# Quick_Dev_board_2021-04-23.net
KiCad netlist of a schematic drawn in EasyEDA
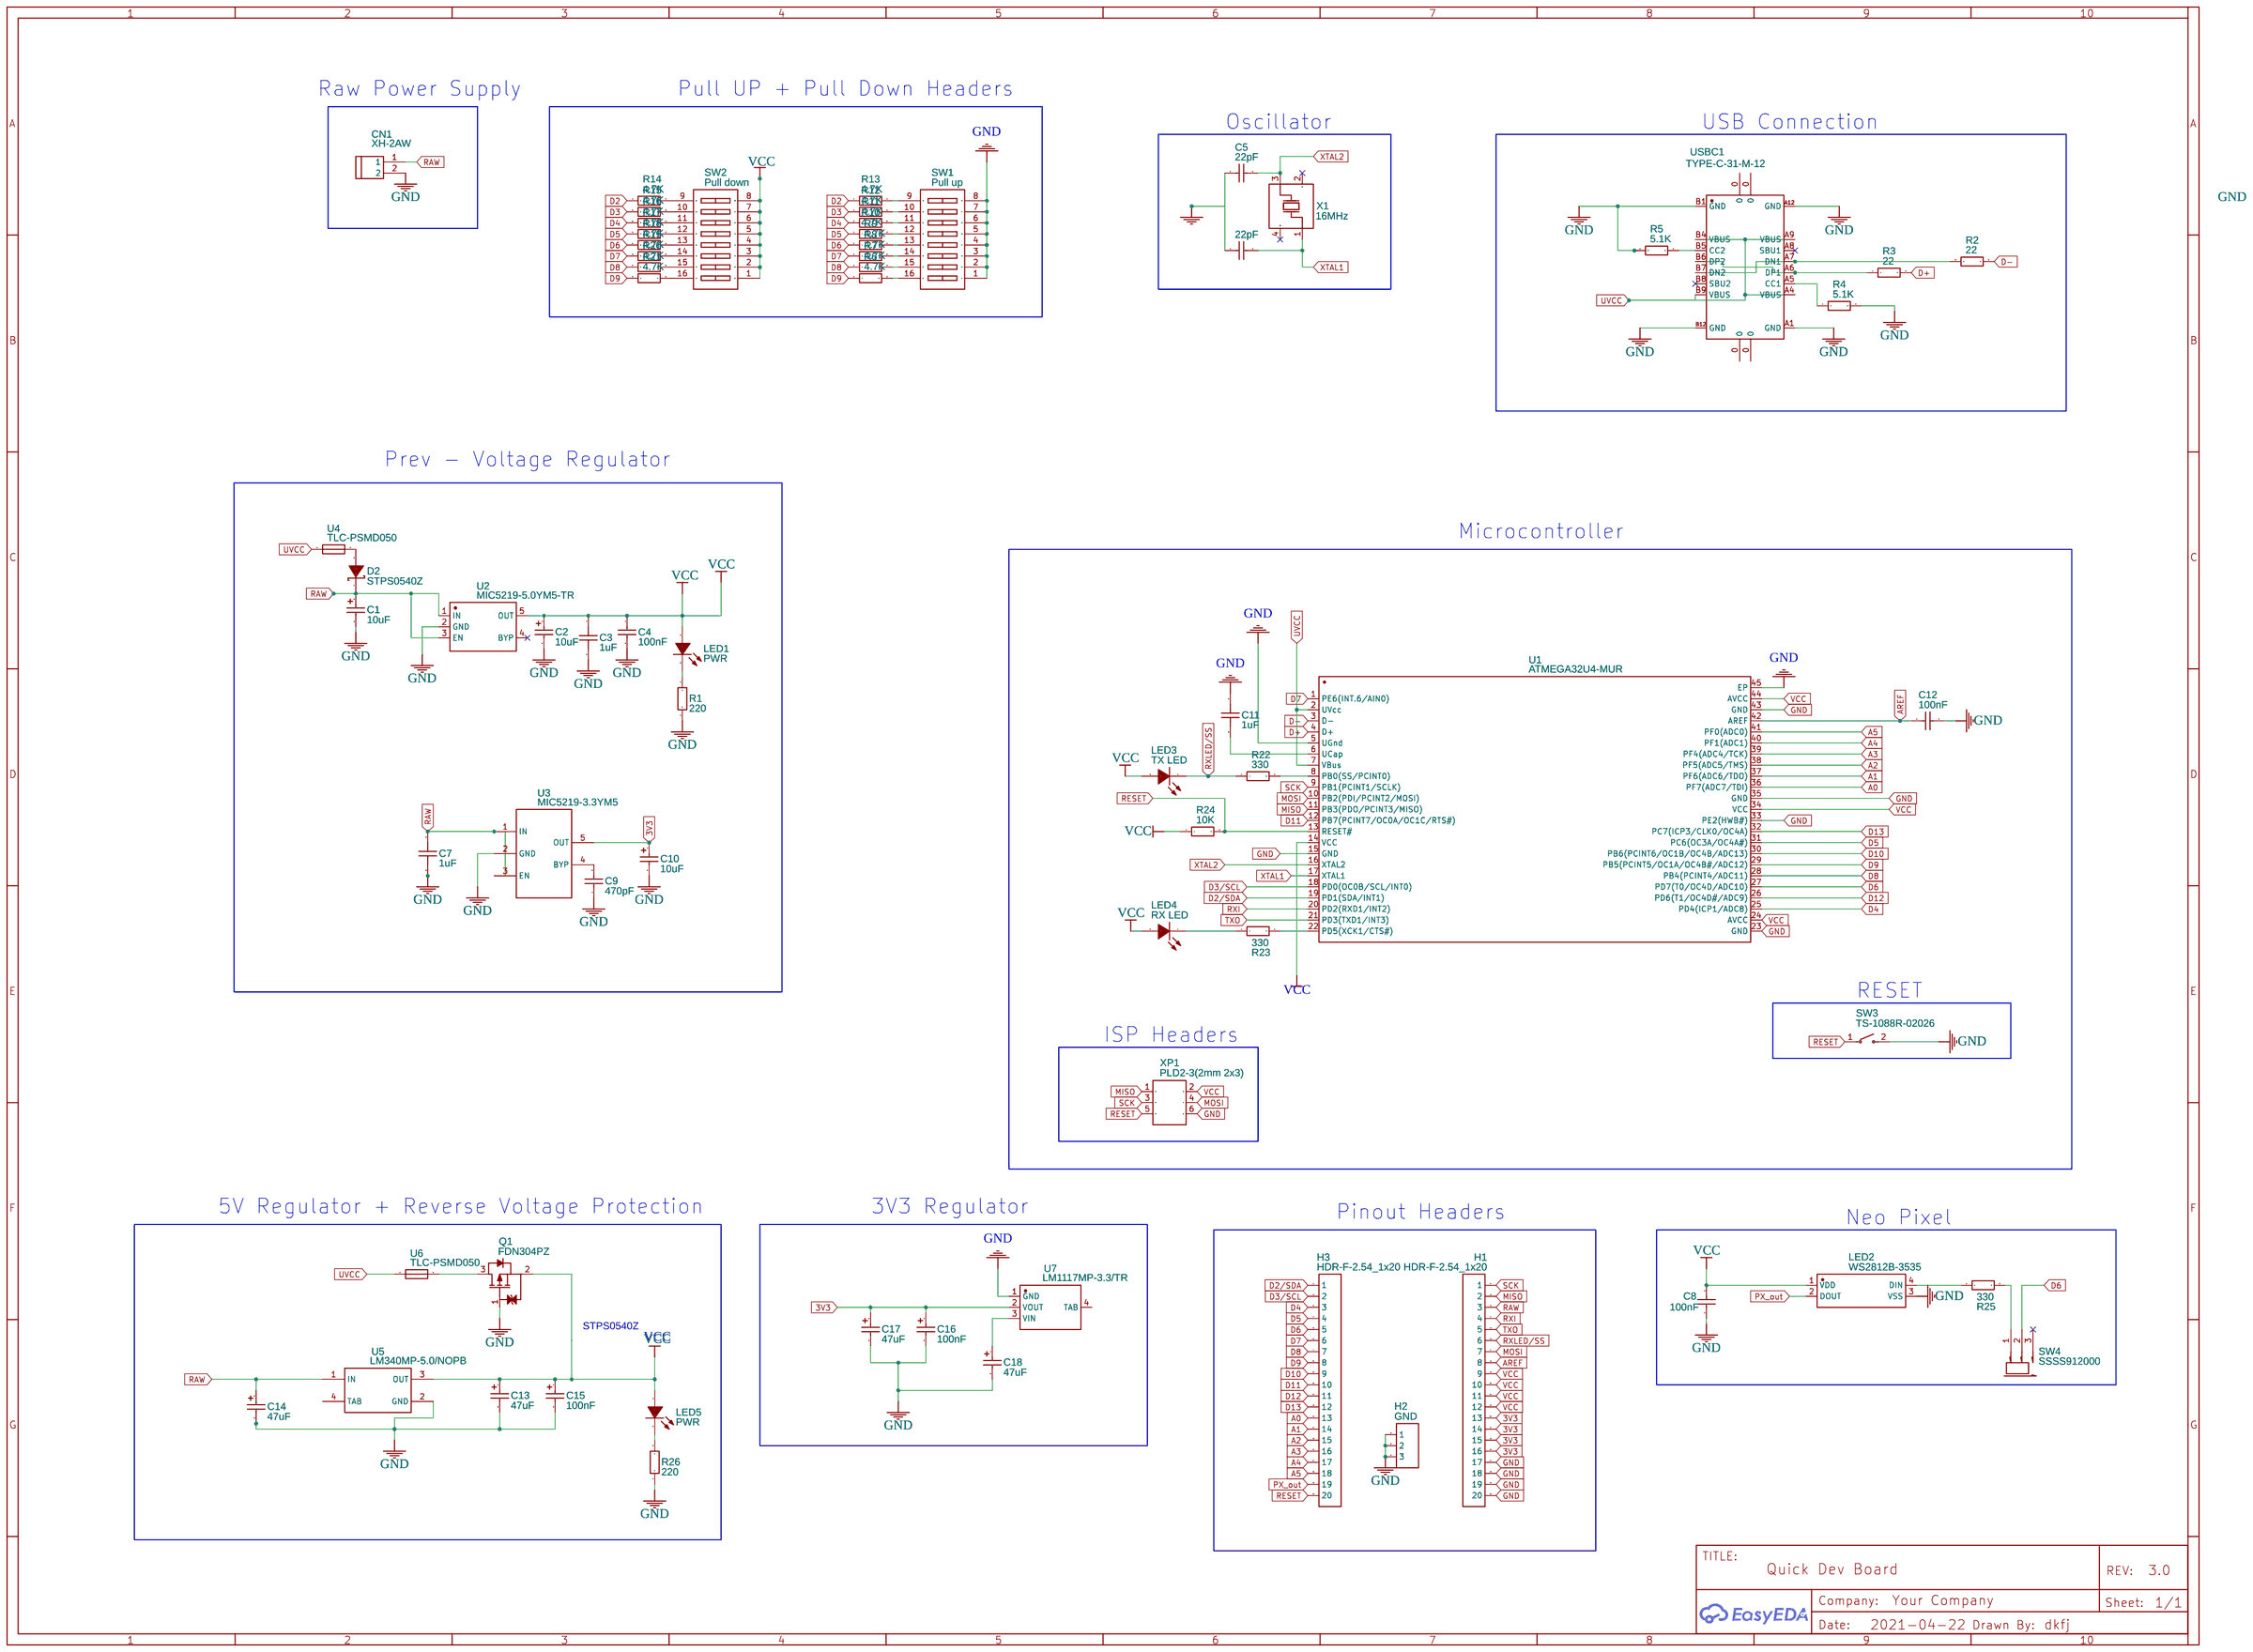
[diagram p0: schematic sheet]

(export (version "E")
  (design (tool "Eeschema 10.0.6"))
  (components
    (comp (ref "C1")
      (value "10uF")
      (fields
        (field (name "BOM_Manufacturer Part") "TAJA106K016RNJ")
        (field (name "BOM_Supplier Part") "C7171")
      )
      (libsource (lib "") (part "TAJA106K016RNJ"))
    )
    (comp (ref "C2")
      (value "10uF")
      (fields
        (field (name "BOM_Manufacturer Part") "TAJA106K016RNJ")
        (field (name "BOM_Supplier Part") "C7171")
      )
      (libsource (lib "") (part "TAJA106K016RNJ"))
    )
    (comp (ref "C3")
      (value "1uF")
      (fields
        (field (name "BOM_Manufacturer Part") "CL05A105KA5NQNC")
        (field (name "BOM_Supplier Part") "C52923")
      )
      (libsource (lib "") (part "CL05A105KA5NQNC"))
    )
    (comp (ref "C4")
      (value "100nF")
      (fields
        (field (name "BOM_Manufacturer Part") "CL05B104KO5NNNC")
        (field (name "BOM_Supplier Part") "C1525")
      )
      (libsource (lib "") (part "CL05B104KO5NNNC_1"))
    )
    (comp (ref "C5")
      (value "22pF")
      (fields
        (field (name "BOM_Manufacturer Part") "0402CG220J500NT")
        (field (name "BOM_Supplier Part") "C1555")
      )
      (libsource (lib "") (part "0402CG220J500NT"))
    )
    (comp (ref "C6")
      (value "22pF")
      (fields
        (field (name "BOM_Manufacturer Part") "0402CG220J500NT")
        (field (name "BOM_Supplier Part") "C1555")
      )
      (libsource (lib "") (part "0402CG220J500NT"))
    )
    (comp (ref "C7")
      (value "1uF")
      (fields
        (field (name "BOM_Manufacturer Part") "CL05A105KA5NQNC")
        (field (name "BOM_Supplier Part") "C52923")
      )
      (libsource (lib "") (part "CL05A105KA5NQNC"))
    )
    (comp (ref "C8")
      (value "100nF")
      (fields
        (field (name "BOM_Manufacturer Part") "CL05B104KO5NNNC")
        (field (name "BOM_Supplier Part") "C1525")
      )
      (libsource (lib "") (part "CL05B104KO5NNNC_1"))
    )
    (comp (ref "C9")
      (value "470pF")
      (fields
        (field (name "BOM_Manufacturer Part") "0402B471K500NT")
        (field (name "BOM_Supplier Part") "C1537")
      )
      (libsource (lib "") (part "0402B471K500NT"))
    )
    (comp (ref "C10")
      (value "10uF")
      (fields
        (field (name "BOM_Manufacturer Part") "TAJA106K016RNJ")
        (field (name "BOM_Supplier Part") "C7171")
      )
      (libsource (lib "") (part "TAJA106K016RNJ"))
    )
    (comp (ref "C11")
      (value "1uF")
      (fields
        (field (name "BOM_Manufacturer Part") "CL05A105KA5NQNC")
        (field (name "BOM_Supplier Part") "C52923")
      )
      (libsource (lib "") (part "CL05A105KA5NQNC"))
    )
    (comp (ref "C12")
      (value "100nF")
      (fields
        (field (name "BOM_Manufacturer Part") "CL05B104KO5NNNC")
        (field (name "BOM_Supplier Part") "C1525")
      )
      (libsource (lib "") (part "CL05B104KO5NNNC"))
    )
    (comp (ref "C13")
      (value "47uF")
      (fields
        (field (name "BOM_Manufacturer Part") "TAJA106K016RNJ")
        (field (name "BOM_Supplier Part") "C7171")
      )
      (libsource (lib "") (part "TAJA106K016RNJ"))
    )
    (comp (ref "C14")
      (value "47uF")
      (fields
        (field (name "BOM_Manufacturer Part") "TAJA106K016RNJ")
        (field (name "BOM_Supplier Part") "C7171")
      )
      (libsource (lib "") (part "TAJA106K016RNJ"))
    )
    (comp (ref "C15")
      (value "100nF")
      (fields
        (field (name "BOM_Manufacturer Part") "TAJA106K016RNJ")
        (field (name "BOM_Supplier Part") "C7171")
      )
      (libsource (lib "") (part "TAJA106K016RNJ"))
    )
    (comp (ref "C16")
      (value "100nF")
      (fields
        (field (name "BOM_Manufacturer Part") "TAJA106K016RNJ")
        (field (name "BOM_Supplier Part") "C7171")
      )
      (libsource (lib "") (part "TAJA106K016RNJ"))
    )
    (comp (ref "C17")
      (value "47uF")
      (fields
        (field (name "BOM_Manufacturer Part") "TAJA106K016RNJ")
        (field (name "BOM_Supplier Part") "C7171")
      )
      (libsource (lib "") (part "TAJA106K016RNJ"))
    )
    (comp (ref "C18")
      (value "47uF")
      (fields
        (field (name "BOM_Manufacturer Part") "TAJA106K016RNJ")
        (field (name "BOM_Supplier Part") "C7171")
      )
      (libsource (lib "") (part "TAJA106K016RNJ"))
    )
    (comp (ref "CN1")
      (value "XH-2AW")
      (fields (field (name "BOM_Supplier Part") "C33132"))
      (libsource (lib "") (part "XH-2AW"))
    )
    (comp (ref "D2")
      (value "STPS0540Z")
      (fields (field (name "BOM_Supplier Part") "C181835"))
      (libsource (lib "") (part "STPS0540Z"))
    )
    (comp (ref "H1")
      (value "HDR-F-2.54_1x20")
      (fields (field (name "BOM_Supplier Part") "C50984"))
      (libsource (lib "") (part "HDR-F-2.54_1x20"))
    )
    (comp (ref "H2")
      (value "GND")
      (fields (field (name "BOM_Supplier Part") "C146690"))
      (libsource (lib "") (part "HDR-F-2.54_1x3"))
    )
    (comp (ref "H3")
      (value "HDR-F-2.54_1x20")
      (fields (field (name "BOM_Supplier Part") "C50984"))
      (libsource (lib "") (part "HDR-F-2.54_1x20_1"))
    )
    (comp (ref "LED1")
      (value "PWR")
      (fields (field (name "BOM_Manufacturer Part") "KT-0603R") (field (name "BOM_Supplier Part") "C2286"))
      (libsource (lib "") (part "KT-0603R"))
    )
    (comp (ref "LED2")
      (value "WS2812B-3535")
      (fields (field (name "BOM_Supplier Part") "C114583"))
      (libsource (lib "") (part "WS2812B-3535"))
    )
    (comp (ref "LED3")
      (value "TX LED")
      (fields
        (field (name "BOM_Manufacturer Part") "17-21SUYC/TR8")
        (field (name "BOM_Supplier Part") "C2296")
      )
      (libsource (lib "") (part "17-21SUYC/TR8"))
    )
    (comp (ref "LED4")
      (value "RX LED")
      (fields
        (field (name "BOM_Manufacturer Part") "17-21SUYC/TR8")
        (field (name "BOM_Supplier Part") "C2296")
      )
      (libsource (lib "") (part "17-21SUYC/TR8"))
    )
    (comp (ref "LED5")
      (value "PWR")
      (fields (field (name "BOM_Manufacturer Part") "KT-0603R") (field (name "BOM_Supplier Part") "C2286"))
      (libsource (lib "") (part "KT-0603R"))
    )
    (comp (ref "Q1")
      (value "FDN304PZ")
      (fields (field (name "BOM_Supplier Part") "C73273"))
      (libsource (lib "") (part "FDN304PZ"))
    )
    (comp (ref "R1")
      (value "220")
      (fields
        (field (name "BOM_Manufacturer Part") "0603WAF2200T5E")
        (field (name "BOM_Supplier Part") "C22962")
      )
      (libsource (lib "") (part "0603WAF2200T5E"))
    )
    (comp (ref "R2")
      (value "22")
      (fields
        (field (name "BOM_Manufacturer Part") "0402WGF220JTCE")
        (field (name "BOM_Supplier Part") "C25092")
      )
      (libsource (lib "") (part "0402WGF220JTCE"))
    )
    (comp (ref "R3")
      (value "22")
      (fields
        (field (name "BOM_Manufacturer Part") "0402WGF220JTCE")
        (field (name "BOM_Supplier Part") "C25092")
      )
      (libsource (lib "") (part "0402WGF220JTCE"))
    )
    (comp (ref "R4")
      (value "5.1K")
      (fields
        (field (name "BOM_Manufacturer Part") "0402WGF5101TCE")
        (field (name "BOM_Supplier Part") "C25905")
      )
      (libsource (lib "") (part "0402WGF5101TCE"))
    )
    (comp (ref "R5")
      (value "5.1K")
      (fields
        (field (name "BOM_Manufacturer Part") "0402WGF5101TCE")
        (field (name "BOM_Supplier Part") "C25905")
      )
      (libsource (lib "") (part "0402WGF5101TCE"))
    )
    (comp (ref "R6")
      (value "4.7K")
      (fields
        (field (name "BOM_Manufacturer Part") "0402WGF4701TCE")
        (field (name "BOM_Supplier Part") "C25900")
      )
      (libsource (lib "") (part "0402WGF4701TCE"))
    )
    (comp (ref "R7")
      (value "4.7K")
      (fields
        (field (name "BOM_Manufacturer Part") "0402WGF4701TCE")
        (field (name "BOM_Supplier Part") "C25900")
      )
      (libsource (lib "") (part "0402WGF4701TCE"))
    )
    (comp (ref "R8")
      (value "4.7K")
      (fields
        (field (name "BOM_Manufacturer Part") "0402WGF4701TCE")
        (field (name "BOM_Supplier Part") "C25900")
      )
      (libsource (lib "") (part "0402WGF4701TCE"))
    )
    (comp (ref "R9")
      (value "4.7K")
      (fields
        (field (name "BOM_Manufacturer Part") "0402WGF4701TCE")
        (field (name "BOM_Supplier Part") "C25900")
      )
      (libsource (lib "") (part "0402WGF4701TCE"))
    )
    (comp (ref "R10")
      (value "4.7K")
      (fields
        (field (name "BOM_Manufacturer Part") "0402WGF4701TCE")
        (field (name "BOM_Supplier Part") "C25900")
      )
      (libsource (lib "") (part "0402WGF4701TCE"))
    )
    (comp (ref "R11")
      (value "4.7K")
      (fields
        (field (name "BOM_Manufacturer Part") "0402WGF4701TCE")
        (field (name "BOM_Supplier Part") "C25900")
      )
      (libsource (lib "") (part "0402WGF4701TCE"))
    )
    (comp (ref "R12")
      (value "4.7K")
      (fields
        (field (name "BOM_Manufacturer Part") "0402WGF4701TCE")
        (field (name "BOM_Supplier Part") "C25900")
      )
      (libsource (lib "") (part "0402WGF4701TCE"))
    )
    (comp (ref "R13")
      (value "4.7K")
      (fields
        (field (name "BOM_Manufacturer Part") "0402WGF4701TCE")
        (field (name "BOM_Supplier Part") "C25900")
      )
      (libsource (lib "") (part "0402WGF4701TCE"))
    )
    (comp (ref "R14")
      (value "4.7K")
      (fields
        (field (name "BOM_Manufacturer Part") "0402WGF4701TCE")
        (field (name "BOM_Supplier Part") "C25900")
      )
      (libsource (lib "") (part "0402WGF4701TCE"))
    )
    (comp (ref "R15")
      (value "4.7K")
      (fields
        (field (name "BOM_Manufacturer Part") "0402WGF4701TCE")
        (field (name "BOM_Supplier Part") "C25900")
      )
      (libsource (lib "") (part "0402WGF4701TCE"))
    )
    (comp (ref "R16")
      (value "4.7K")
      (fields
        (field (name "BOM_Manufacturer Part") "0402WGF4701TCE")
        (field (name "BOM_Supplier Part") "C25900")
      )
      (libsource (lib "") (part "0402WGF4701TCE"))
    )
    (comp (ref "R17")
      (value "4.7K")
      (fields
        (field (name "BOM_Manufacturer Part") "0402WGF4701TCE")
        (field (name "BOM_Supplier Part") "C25900")
      )
      (libsource (lib "") (part "0402WGF4701TCE"))
    )
    (comp (ref "R18")
      (value "4.7K")
      (fields
        (field (name "BOM_Manufacturer Part") "0402WGF4701TCE")
        (field (name "BOM_Supplier Part") "C25900")
      )
      (libsource (lib "") (part "0402WGF4701TCE"))
    )
    (comp (ref "R19")
      (value "4.7K")
      (fields
        (field (name "BOM_Manufacturer Part") "0402WGF4701TCE")
        (field (name "BOM_Supplier Part") "C25900")
      )
      (libsource (lib "") (part "0402WGF4701TCE"))
    )
    (comp (ref "R20")
      (value "4.7K")
      (fields
        (field (name "BOM_Manufacturer Part") "0402WGF4701TCE")
        (field (name "BOM_Supplier Part") "C25900")
      )
      (libsource (lib "") (part "0402WGF4701TCE"))
    )
    (comp (ref "R21")
      (value "4.7K")
      (fields
        (field (name "BOM_Manufacturer Part") "0402WGF4701TCE")
        (field (name "BOM_Supplier Part") "C25900")
      )
      (libsource (lib "") (part "0402WGF4701TCE"))
    )
    (comp (ref "R22")
      (value "330")
      (fields
        (field (name "BOM_Manufacturer Part") "0402WGF3300TCE")
        (field (name "BOM_Supplier Part") "C25104")
      )
      (libsource (lib "") (part "0402WGF3300TCE"))
    )
    (comp (ref "R23")
      (value "330")
      (fields
        (field (name "BOM_Manufacturer Part") "0402WGF3300TCE")
        (field (name "BOM_Supplier Part") "C25104")
      )
      (libsource (lib "") (part "0402WGF3300TCE"))
    )
    (comp (ref "R24")
      (value "10K")
      (fields
        (field (name "BOM_Manufacturer Part") "0402WGF1002TCE")
        (field (name "BOM_Supplier Part") "C25744")
      )
      (libsource (lib "") (part "0402WGF1002TCE"))
    )
    (comp (ref "R25")
      (value "330")
      (fields
        (field (name "BOM_Manufacturer Part") "0402WGF3300TCE")
        (field (name "BOM_Supplier Part") "C25104")
      )
      (libsource (lib "") (part "0402WGF3300TCE"))
    )
    (comp (ref "R26")
      (value "220")
      (fields
        (field (name "BOM_Manufacturer Part") "0603WAF2200T5E")
        (field (name "BOM_Supplier Part") "C22962")
      )
      (libsource (lib "") (part "0603WAF2200T5E"))
    )
    (comp (ref "SW1")
      (value "Pull up")
      (fields
        (field (name "BOM_Manufacturer Part") "DSHP08TS-S")
        (field (name "BOM_Supplier Part") "C319047")
      )
      (libsource (lib "") (part "DSHP08TS-S"))
    )
    (comp (ref "SW2")
      (value "Pull down")
      (fields
        (field (name "BOM_Manufacturer Part") "DSHP08TS-S")
        (field (name "BOM_Supplier Part") "C319047")
      )
      (libsource (lib "") (part "DSHP08TS-S"))
    )
    (comp (ref "SW3")
      (value "TS-1088R-02026")
      (fields (field (name "BOM_Supplier Part") "C455280"))
      (libsource (lib "") (part "TS-1088R-02026"))
    )
    (comp (ref "SW4")
      (value "SSSS912000")
      (fields (field (name "BOM_Supplier Part") "C125042"))
      (libsource (lib "") (part "SSSS912000"))
    )
    (comp (ref "U1")
      (value "ATMEGA32U4-MUR")
      (fields (field (name "BOM_Supplier Part") "C45874"))
      (libsource (lib "") (part "ATMEGA32U4-MUR"))
    )
    (comp (ref "U2")
      (value "MIC5219-5.0YM5-TR")
      (fields (field (name "BOM_Supplier Part") "C144182"))
      (libsource (lib "") (part "MIC5219-5.0YM5-TR"))
    )
    (comp (ref "U3")
      (value "MIC5219-3.3YM5")
      (fields (field (name "BOM_Supplier Part") "C29613"))
      (libsource (lib "") (part "MIC5219-3.3YM5"))
    )
    (comp (ref "U4")
      (value "TLC-PSMD050")
      (fields (field (name "BOM_Supplier Part") "C261942"))
      (libsource (lib "") (part "TLC-PSMD050"))
    )
    (comp (ref "U5")
      (value "LM340MP-5.0/NOPB")
      (fields (field (name "BOM_Supplier Part") "C131990"))
      (libsource (lib "") (part "LM340MP-5.0/NOPB"))
    )
    (comp (ref "U6")
      (value "TLC-PSMD050")
      (fields (field (name "BOM_Supplier Part") "C261942"))
      (libsource (lib "") (part "TLC-PSMD050"))
    )
    (comp (ref "U7")
      (value "LM1117MP-3.3/TR")
      (fields (field (name "BOM_Supplier Part") "C498153"))
      (libsource (lib "") (part "LM1117MP-3.3/TR"))
    )
    (comp (ref "USBC1")
      (value "TYPE-C-31-M-12")
      (fields (field (name "BOM_Supplier Part") "C165948"))
      (libsource (lib "") (part "TYPE-C-31-M-12"))
    )
    (comp (ref "X1")
      (value "16MHz")
      (fields
        (field (name "BOM_Manufacturer Part") "X322516MLB4SI")
        (field (name "BOM_Supplier Part") "C13738")
      )
      (libsource (lib "") (part "X322516MLB4SI"))
    )
    (comp (ref "XP1")
      (value "PLD2-3(2mm 2x3)")
      (fields (field (name "BOM_Manufacturer Part") "PLD-3 2,54 2x3"))
      (libsource (lib "") (part "PLD2-3(2mm 2x3)"))
    )
  )
  (nets
    (net (code "1") (name "3V3") (class "Default")
      (node (ref "C10") (pin "1") (pinfunction "1_1") (pintype "input"))
      (node (ref "C16") (pin "1") (pinfunction "1_1") (pintype "input"))
      (node (ref "C17") (pin "1") (pinfunction "1_1") (pintype "input"))
      (node (ref "H1") (pin "13") (pinfunction "13_13") (pintype "unspecified"))
      (node (ref "H1") (pin "14") (pinfunction "14_14") (pintype "unspecified"))
      (node (ref "H1") (pin "15") (pinfunction "15_15") (pintype "unspecified"))
      (node (ref "H1") (pin "16") (pinfunction "16_16") (pintype "unspecified"))
      (node (ref "U3") (pin "5") (pinfunction "OUT_5") (pintype "unspecified"))
      (node (ref "U7") (pin "2") (pinfunction "VOUT_2") (pintype "unspecified"))
    )
    (net (code "2") (name "A0") (class "Default")
      (node (ref "H3") (pin "13") (pinfunction "13_13") (pintype "unspecified"))
      (node (ref "U1") (pin "36") (pinfunction "PF7(ADC7/TDI)_36") (pintype "unspecified"))
    )
    (net (code "3") (name "A1") (class "Default")
      (node (ref "H3") (pin "14") (pinfunction "14_14") (pintype "unspecified"))
      (node (ref "U1") (pin "37") (pinfunction "PF6(ADC6/TDO)_37") (pintype "unspecified"))
    )
    (net (code "4") (name "A2") (class "Default")
      (node (ref "H3") (pin "15") (pinfunction "15_15") (pintype "unspecified"))
      (node (ref "U1") (pin "38") (pinfunction "PF5(ADC5/TMS)_38") (pintype "unspecified"))
    )
    (net (code "5") (name "A3") (class "Default")
      (node (ref "H3") (pin "16") (pinfunction "16_16") (pintype "unspecified"))
      (node (ref "U1") (pin "39") (pinfunction "PF4(ADC4/TCK)_39") (pintype "unspecified"))
    )
    (net (code "6") (name "A4") (class "Default")
      (node (ref "H3") (pin "17") (pinfunction "17_17") (pintype "unspecified"))
      (node (ref "U1") (pin "40") (pinfunction "PF1(ADC1)_40") (pintype "unspecified"))
    )
    (net (code "7") (name "A5") (class "Default")
      (node (ref "H3") (pin "18") (pinfunction "18_18") (pintype "unspecified"))
      (node (ref "U1") (pin "41") (pinfunction "PF0(ADC0)_41") (pintype "unspecified"))
    )
    (net (code "8") (name "AREF") (class "Default")
      (node (ref "C12") (pin "1") (pinfunction "1_1") (pintype "input"))
      (node (ref "H1") (pin "8") (pinfunction "8_8") (pintype "unspecified"))
      (node (ref "U1") (pin "42") (pinfunction "AREF_42") (pintype "unspecified"))
    )
    (net (code "9") (name "D+") (class "Default")
      (node (ref "R3") (pin "2") (pinfunction "2_2") (pintype "input"))
      (node (ref "U1") (pin "4") (pinfunction "D+_4") (pintype "unspecified"))
    )
    (net (code "10") (name "D-") (class "Default")
      (node (ref "R2") (pin "2") (pinfunction "2_2") (pintype "input"))
      (node (ref "U1") (pin "3") (pinfunction "D-_3") (pintype "unspecified"))
    )
    (net (code "11") (name "D2") (class "Default")
      (node (ref "R13") (pin "1") (pinfunction "1_1") (pintype "input"))
      (node (ref "R14") (pin "1") (pinfunction "1_1") (pintype "input"))
    )
    (net (code "12") (name "D2{slash}SDA") (class "Default")
      (node (ref "H3") (pin "1") (pinfunction "1_1") (pintype "unspecified"))
      (node (ref "U1") (pin "19") (pinfunction "PD1(SDA/INT1)_19") (pintype "unspecified"))
    )
    (net (code "13") (name "D3") (class "Default")
      (node (ref "R12") (pin "1") (pinfunction "1_1") (pintype "input"))
      (node (ref "R15") (pin "1") (pinfunction "1_1") (pintype "input"))
    )
    (net (code "14") (name "D3{slash}SCL") (class "Default")
      (node (ref "H3") (pin "2") (pinfunction "2_2") (pintype "unspecified"))
      (node (ref "U1") (pin "18") (pinfunction "PD0(OC0B/SCL/INT0)_18") (pintype "unspecified"))
    )
    (net (code "15") (name "D4") (class "Default")
      (node (ref "H3") (pin "3") (pinfunction "3_3") (pintype "unspecified"))
      (node (ref "R11") (pin "1") (pinfunction "1_1") (pintype "input"))
      (node (ref "R16") (pin "1") (pinfunction "1_1") (pintype "input"))
      (node (ref "U1") (pin "25") (pinfunction "PD4(ICP1/ADC8)_25") (pintype "unspecified"))
    )
    (net (code "16") (name "D5") (class "Default")
      (node (ref "H3") (pin "4") (pinfunction "4_4") (pintype "unspecified"))
      (node (ref "R10") (pin "1") (pinfunction "1_1") (pintype "input"))
      (node (ref "R17") (pin "1") (pinfunction "1_1") (pintype "input"))
      (node (ref "U1") (pin "31") (pinfunction "PC6(OC3A/OC4A#)_31") (pintype "unspecified"))
    )
    (net (code "17") (name "D6") (class "Default")
      (node (ref "H3") (pin "5") (pinfunction "5_5") (pintype "unspecified"))
      (node (ref "R18") (pin "1") (pinfunction "1_1") (pintype "input"))
      (node (ref "R9") (pin "1") (pinfunction "1_1") (pintype "input"))
      (node (ref "SW4") (pin "2") (pinfunction "2_2") (pintype "unspecified"))
      (node (ref "U1") (pin "27") (pinfunction "PD7(T0/OC4D/ADC10)_27") (pintype "unspecified"))
    )
    (net (code "18") (name "D7") (class "Default")
      (node (ref "H3") (pin "6") (pinfunction "6_6") (pintype "unspecified"))
      (node (ref "R19") (pin "1") (pinfunction "1_1") (pintype "input"))
      (node (ref "R8") (pin "1") (pinfunction "1_1") (pintype "input"))
      (node (ref "U1") (pin "1") (pinfunction "PE6(INT.6/AIN0)_1") (pintype "unspecified"))
    )
    (net (code "19") (name "D8") (class "Default")
      (node (ref "H3") (pin "7") (pinfunction "7_7") (pintype "unspecified"))
      (node (ref "R20") (pin "1") (pinfunction "1_1") (pintype "input"))
      (node (ref "R7") (pin "1") (pinfunction "1_1") (pintype "input"))
      (node (ref "U1") (pin "28") (pinfunction "PB4(PCINT4/ADC11)_28") (pintype "unspecified"))
    )
    (net (code "20") (name "D9") (class "Default")
      (node (ref "H3") (pin "8") (pinfunction "8_8") (pintype "unspecified"))
      (node (ref "R21") (pin "1") (pinfunction "1_1") (pintype "input"))
      (node (ref "R6") (pin "1") (pinfunction "1_1") (pintype "input"))
      (node (ref "U1") (pin "29") (pinfunction "PB5(PCINT5/OC1A/OC4B#/ADC12)_29") (pintype "unspecified"))
    )
    (net (code "21") (name "D10") (class "Default")
      (node (ref "H3") (pin "9") (pinfunction "9_9") (pintype "unspecified"))
      (node (ref "U1") (pin "30") (pinfunction "PB6(PCINT6/OC1B/OC4B/ADC13)_30") (pintype "unspecified"))
    )
    (net (code "22") (name "D11") (class "Default")
      (node (ref "H3") (pin "10") (pinfunction "10_10") (pintype "unspecified"))
      (node (ref "U1") (pin "12") (pinfunction "PB7(PCINT7/OC0A/OC1C/RTS#)_12") (pintype "unspecified"))
    )
    (net (code "23") (name "D12") (class "Default")
      (node (ref "H3") (pin "11") (pinfunction "11_11") (pintype "unspecified"))
      (node (ref "U1") (pin "26") (pinfunction "PD6(T1/OC4D#/ADC9)_26") (pintype "unspecified"))
    )
    (net (code "24") (name "D13") (class "Default")
      (node (ref "H3") (pin "12") (pinfunction "12_12") (pintype "unspecified"))
      (node (ref "U1") (pin "32") (pinfunction "PC7(ICP3/CLK0/OC4A)_32") (pintype "unspecified"))
    )
    (net (code "25") (name "GND") (class "Default")
      (node (ref "C1") (pin "2") (pinfunction "2_2") (pintype "input"))
      (node (ref "C10") (pin "2") (pinfunction "2_2") (pintype "input"))
      (node (ref "C11") (pin "1") (pinfunction "1_1") (pintype "unspecified"))
      (node (ref "C12") (pin "2") (pinfunction "2_2") (pintype "input"))
      (node (ref "C13") (pin "2") (pinfunction "2_2") (pintype "input"))
      (node (ref "C14") (pin "2") (pinfunction "2_2") (pintype "input"))
      (node (ref "C15") (pin "2") (pinfunction "2_2") (pintype "input"))
      (node (ref "C16") (pin "2") (pinfunction "2_2") (pintype "input"))
      (node (ref "C17") (pin "2") (pinfunction "2_2") (pintype "input"))
      (node (ref "C18") (pin "2") (pinfunction "2_2") (pintype "input"))
      (node (ref "C2") (pin "2") (pinfunction "2_2") (pintype "input"))
      (node (ref "C3") (pin "2") (pinfunction "2_2") (pintype "unspecified"))
      (node (ref "C4") (pin "2") (pinfunction "2_2") (pintype "input"))
      (node (ref "C5") (pin "1") (pinfunction "1_1") (pintype "input"))
      (node (ref "C6") (pin "1") (pinfunction "1_1") (pintype "input"))
      (node (ref "C7") (pin "2") (pinfunction "2_2") (pintype "unspecified"))
      (node (ref "C8") (pin "2") (pinfunction "2_2") (pintype "input"))
      (node (ref "C9") (pin "1") (pinfunction "1_1") (pintype "input"))
      (node (ref "CN1") (pin "2") (pinfunction "2_2") (pintype "unspecified"))
      (node (ref "H1") (pin "17") (pinfunction "17_17") (pintype "unspecified"))
      (node (ref "H1") (pin "18") (pinfunction "18_18") (pintype "unspecified"))
      (node (ref "H1") (pin "19") (pinfunction "19_19") (pintype "unspecified"))
      (node (ref "H1") (pin "20") (pinfunction "20_20") (pintype "unspecified"))
      (node (ref "H2") (pin "1") (pinfunction "1_1") (pintype "input"))
      (node (ref "H2") (pin "2") (pinfunction "2_2") (pintype "input"))
      (node (ref "H2") (pin "3") (pinfunction "3_3") (pintype "input"))
      (node (ref "LED2") (pin "3") (pinfunction "VSS_3") (pintype "unspecified"))
      (node (ref "Q1") (pin "1") (pinfunction "G_1") (pintype "unspecified"))
      (node (ref "R1") (pin "1") (pinfunction "1_1") (pintype "input"))
      (node (ref "R26") (pin "1") (pinfunction "1_1") (pintype "input"))
      (node (ref "R4") (pin "2") (pinfunction "2_2") (pintype "input"))
      (node (ref "R5") (pin "1") (pinfunction "1_1") (pintype "input"))
      (node (ref "SW1") (pin "1") (pinfunction "A1_1") (pintype "input"))
      (node (ref "SW1") (pin "2") (pinfunction "A2_2") (pintype "input"))
      (node (ref "SW1") (pin "3") (pinfunction "A3_3") (pintype "input"))
      (node (ref "SW1") (pin "4") (pinfunction "A4_4") (pintype "input"))
      (node (ref "SW1") (pin "5") (pinfunction "A5_5") (pintype "input"))
      (node (ref "SW1") (pin "6") (pinfunction "A6_6") (pintype "input"))
      (node (ref "SW1") (pin "7") (pinfunction "A7_7") (pintype "input"))
      (node (ref "SW1") (pin "8") (pinfunction "A8_8") (pintype "input"))
      (node (ref "SW3") (pin "2") (pinfunction "2_2") (pintype "unspecified"))
      (node (ref "U1") (pin "15") (pinfunction "GND_15") (pintype "unspecified"))
      (node (ref "U1") (pin "23") (pinfunction "GND_23") (pintype "unspecified"))
      (node (ref "U1") (pin "33") (pinfunction "PE2(HWB#)_33") (pintype "unspecified"))
      (node (ref "U1") (pin "35") (pinfunction "GND_35") (pintype "unspecified"))
      (node (ref "U1") (pin "43") (pinfunction "GND_43") (pintype "unspecified"))
      (node (ref "U1") (pin "45") (pinfunction "EP_45") (pintype "unspecified"))
      (node (ref "U1") (pin "5") (pinfunction "UGnd_5") (pintype "unspecified"))
      (node (ref "U2") (pin "2") (pinfunction "GND_2") (pintype "unspecified"))
      (node (ref "U3") (pin "2") (pinfunction "GND_2") (pintype "unspecified"))
      (node (ref "U5") (pin "2") (pinfunction "GND_2") (pintype "passive"))
      (node (ref "U7") (pin "1") (pinfunction "GND_1") (pintype "unspecified"))
      (node (ref "USBC1") (pin "A1") (pinfunction "GND_A1") (pintype "unspecified"))
      (node (ref "USBC1") (pin "A12") (pinfunction "GND_A12") (pintype "unspecified"))
      (node (ref "USBC1") (pin "B1") (pinfunction "GND_B1") (pintype "unspecified"))
      (node (ref "USBC1") (pin "B12") (pinfunction "GND_B12") (pintype "unspecified"))
      (node (ref "XP1") (pin "6") (pinfunction "6_6") (pintype "unspecified"))
    )
    (net (code "26") (name "MISO") (class "Default")
      (node (ref "H1") (pin "2") (pinfunction "2_2") (pintype "unspecified"))
      (node (ref "U1") (pin "11") (pinfunction "PB3(PDO/PCINT3/MISO)_11") (pintype "unspecified"))
      (node (ref "XP1") (pin "1") (pinfunction "1_1") (pintype "unspecified"))
    )
    (net (code "27") (name "MOSI") (class "Default")
      (node (ref "H1") (pin "7") (pinfunction "7_7") (pintype "unspecified"))
      (node (ref "U1") (pin "10") (pinfunction "PB2(PDI/PCINT2/MOSI)_10") (pintype "unspecified"))
      (node (ref "XP1") (pin "4") (pinfunction "4_4") (pintype "unspecified"))
    )
    (net (code "28") (name "Net-(D2-A)") (class "Default")
      (node (ref "D2") (pin "2") (pinfunction "A_2") (pintype "unspecified"))
      (node (ref "U4") (pin "2") (pinfunction "2_2") (pintype "unspecified"))
    )
    (net (code "29") (name "Net-(LED1-K)") (class "Default")
      (node (ref "LED1") (pin "2") (pinfunction "K_2") (pintype "unspecified"))
      (node (ref "R1") (pin "2") (pinfunction "2_2") (pintype "input"))
    )
    (net (code "30") (name "Net-(LED2-DIN)") (class "Default")
      (node (ref "LED2") (pin "4") (pinfunction "DIN_4") (pintype "unspecified"))
      (node (ref "R25") (pin "1") (pinfunction "1_1") (pintype "input"))
    )
    (net (code "31") (name "Net-(LED4--)") (class "Default")
      (node (ref "LED4") (pin "1") (pinfunction "-_1") (pintype "unspecified"))
      (node (ref "R23") (pin "1") (pinfunction "1_1") (pintype "input"))
    )
    (net (code "32") (name "Net-(LED5-K)") (class "Default")
      (node (ref "LED5") (pin "2") (pinfunction "K_2") (pintype "unspecified"))
      (node (ref "R26") (pin "2") (pinfunction "2_2") (pintype "input"))
    )
    (net (code "33") (name "Net-(Q1-D)") (class "Default")
      (node (ref "Q1") (pin "3") (pinfunction "D_3") (pintype "unspecified"))
      (node (ref "U6") (pin "2") (pinfunction "2_2") (pintype "unspecified"))
    )
    (net (code "34") (name "Net-(R25-Pad2)") (class "Default")
      (node (ref "R25") (pin "2") (pinfunction "2_2") (pintype "input"))
      (node (ref "SW4") (pin "1") (pinfunction "1_1") (pintype "unspecified"))
    )
    (net (code "35") (name "Net-(SW1-B1)") (class "Default")
      (node (ref "R6") (pin "2") (pinfunction "2_2") (pintype "input"))
      (node (ref "SW1") (pin "16") (pinfunction "B1_16") (pintype "unspecified"))
    )
    (net (code "36") (name "Net-(SW1-B2)") (class "Default")
      (node (ref "R7") (pin "2") (pinfunction "2_2") (pintype "input"))
      (node (ref "SW1") (pin "15") (pinfunction "B2_15") (pintype "unspecified"))
    )
    (net (code "37") (name "Net-(SW1-B3)") (class "Default")
      (node (ref "R8") (pin "2") (pinfunction "2_2") (pintype "input"))
      (node (ref "SW1") (pin "14") (pinfunction "B3_14") (pintype "unspecified"))
    )
    (net (code "38") (name "Net-(SW1-B4)") (class "Default")
      (node (ref "R9") (pin "2") (pinfunction "2_2") (pintype "input"))
      (node (ref "SW1") (pin "13") (pinfunction "B4_13") (pintype "unspecified"))
    )
    (net (code "39") (name "Net-(SW1-B5)") (class "Default")
      (node (ref "R10") (pin "2") (pinfunction "2_2") (pintype "input"))
      (node (ref "SW1") (pin "12") (pinfunction "B5_12") (pintype "input"))
    )
    (net (code "40") (name "Net-(SW1-B6)") (class "Default")
      (node (ref "R11") (pin "2") (pinfunction "2_2") (pintype "input"))
      (node (ref "SW1") (pin "11") (pinfunction "B6_11") (pintype "input"))
    )
    (net (code "41") (name "Net-(SW1-B7)") (class "Default")
      (node (ref "R12") (pin "2") (pinfunction "2_2") (pintype "input"))
      (node (ref "SW1") (pin "10") (pinfunction "B7_10") (pintype "input"))
    )
    (net (code "42") (name "Net-(SW1-B8)") (class "Default")
      (node (ref "R13") (pin "2") (pinfunction "2_2") (pintype "input"))
      (node (ref "SW1") (pin "9") (pinfunction "B8_9") (pintype "input"))
    )
    (net (code "43") (name "Net-(SW2-B1)") (class "Default")
      (node (ref "R21") (pin "2") (pinfunction "2_2") (pintype "input"))
      (node (ref "SW2") (pin "16") (pinfunction "B1_16") (pintype "unspecified"))
    )
    (net (code "44") (name "Net-(SW2-B2)") (class "Default")
      (node (ref "R20") (pin "2") (pinfunction "2_2") (pintype "input"))
      (node (ref "SW2") (pin "15") (pinfunction "B2_15") (pintype "unspecified"))
    )
    (net (code "45") (name "Net-(SW2-B3)") (class "Default")
      (node (ref "R19") (pin "2") (pinfunction "2_2") (pintype "input"))
      (node (ref "SW2") (pin "14") (pinfunction "B3_14") (pintype "unspecified"))
    )
    (net (code "46") (name "Net-(SW2-B4)") (class "Default")
      (node (ref "R18") (pin "2") (pinfunction "2_2") (pintype "input"))
      (node (ref "SW2") (pin "13") (pinfunction "B4_13") (pintype "unspecified"))
    )
    (net (code "47") (name "Net-(SW2-B5)") (class "Default")
      (node (ref "R17") (pin "2") (pinfunction "2_2") (pintype "input"))
      (node (ref "SW2") (pin "12") (pinfunction "B5_12") (pintype "input"))
    )
    (net (code "48") (name "Net-(SW2-B6)") (class "Default")
      (node (ref "R16") (pin "2") (pinfunction "2_2") (pintype "input"))
      (node (ref "SW2") (pin "11") (pinfunction "B6_11") (pintype "input"))
    )
    (net (code "49") (name "Net-(SW2-B7)") (class "Default")
      (node (ref "R15") (pin "2") (pinfunction "2_2") (pintype "input"))
      (node (ref "SW2") (pin "10") (pinfunction "B7_10") (pintype "input"))
    )
    (net (code "50") (name "Net-(SW2-B8)") (class "Default")
      (node (ref "R14") (pin "2") (pinfunction "2_2") (pintype "input"))
      (node (ref "SW2") (pin "9") (pinfunction "B8_9") (pintype "input"))
    )
    (net (code "51") (name "Net-(U1-PB0(SS{slash}PCINT0))") (class "Default")
      (node (ref "R22") (pin "2") (pinfunction "2_2") (pintype "input"))
      (node (ref "U1") (pin "8") (pinfunction "PB0(SS/PCINT0)_8") (pintype "unspecified"))
    )
    (net (code "52") (name "Net-(U1-PD5(XCK1{slash}CTS#))") (class "Default")
      (node (ref "R23") (pin "2") (pinfunction "2_2") (pintype "input"))
      (node (ref "U1") (pin "22") (pinfunction "PD5(XCK1/CTS#)_22") (pintype "unspecified"))
    )
    (net (code "53") (name "Net-(U1-UCap)") (class "Default")
      (node (ref "C11") (pin "2") (pinfunction "2_2") (pintype "unspecified"))
      (node (ref "U1") (pin "6") (pinfunction "UCap_6") (pintype "unspecified"))
    )
    (net (code "54") (name "Net-(U3-BYP)") (class "Default")
      (node (ref "C9") (pin "2") (pinfunction "2_2") (pintype "input"))
      (node (ref "U3") (pin "4") (pinfunction "BYP_4") (pintype "unspecified"))
    )
    (net (code "55") (name "Net-(U7-VIN)") (class "Default")
      (node (ref "C18") (pin "1") (pinfunction "1_1") (pintype "input"))
      (node (ref "U7") (pin "3") (pinfunction "VIN_3") (pintype "unspecified"))
    )
    (net (code "56") (name "Net-(USBC1-CC1)") (class "Default")
      (node (ref "R4") (pin "1") (pinfunction "1_1") (pintype "input"))
      (node (ref "USBC1") (pin "A5") (pinfunction "CC1_A5") (pintype "unspecified"))
    )
    (net (code "57") (name "Net-(USBC1-CC2)") (class "Default")
      (node (ref "R5") (pin "2") (pinfunction "2_2") (pintype "input"))
      (node (ref "USBC1") (pin "B5") (pinfunction "CC2_B5") (pintype "unspecified"))
    )
    (net (code "58") (name "Net-(USBC1-DN1)") (class "Default")
      (node (ref "R2") (pin "1") (pinfunction "1_1") (pintype "input"))
      (node (ref "USBC1") (pin "A7") (pinfunction "DN1_A7") (pintype "unspecified"))
      (node (ref "USBC1") (pin "B7") (pinfunction "DN2_B7") (pintype "unspecified"))
    )
    (net (code "59") (name "Net-(USBC1-DP1)") (class "Default")
      (node (ref "R3") (pin "1") (pinfunction "1_1") (pintype "input"))
      (node (ref "USBC1") (pin "A6") (pinfunction "DP1_A6") (pintype "unspecified"))
      (node (ref "USBC1") (pin "B6") (pinfunction "DP2_B6") (pintype "unspecified"))
    )
    (net (code "60") (name "PX_out") (class "Default")
      (node (ref "H3") (pin "19") (pinfunction "19_19") (pintype "unspecified"))
      (node (ref "LED2") (pin "2") (pinfunction "DOUT_2") (pintype "unspecified"))
    )
    (net (code "61") (name "RAW") (class "Default")
      (node (ref "C1") (pin "1") (pinfunction "1_1") (pintype "input"))
      (node (ref "C14") (pin "1") (pinfunction "1_1") (pintype "input"))
      (node (ref "C7") (pin "1") (pinfunction "1_1") (pintype "unspecified"))
      (node (ref "CN1") (pin "1") (pinfunction "1_1") (pintype "unspecified"))
      (node (ref "D2") (pin "1") (pinfunction "K_1") (pintype "unspecified"))
      (node (ref "H1") (pin "3") (pinfunction "3_3") (pintype "unspecified"))
      (node (ref "U2") (pin "1") (pinfunction "IN_1") (pintype "unspecified"))
      (node (ref "U2") (pin "3") (pinfunction "EN_3") (pintype "unspecified"))
      (node (ref "U3") (pin "1") (pinfunction "IN_1") (pintype "unspecified"))
      (node (ref "U3") (pin "3") (pinfunction "EN_3") (pintype "unspecified"))
      (node (ref "U5") (pin "1") (pinfunction "IN_1") (pintype "passive"))
    )
    (net (code "62") (name "RESET") (class "Default")
      (node (ref "H3") (pin "20") (pinfunction "20_20") (pintype "unspecified"))
      (node (ref "R24") (pin "2") (pinfunction "2_2") (pintype "input"))
      (node (ref "SW3") (pin "1") (pinfunction "1_1") (pintype "unspecified"))
      (node (ref "U1") (pin "13") (pinfunction "RESET#_13") (pintype "unspecified"))
      (node (ref "XP1") (pin "5") (pinfunction "5_5") (pintype "unspecified"))
    )
    (net (code "63") (name "RXI") (class "Default")
      (node (ref "H1") (pin "4") (pinfunction "4_4") (pintype "unspecified"))
      (node (ref "U1") (pin "20") (pinfunction "PD2(RXD1/INT2)_20") (pintype "unspecified"))
    )
    (net (code "64") (name "RXLED{slash}SS") (class "Default")
      (node (ref "H1") (pin "6") (pinfunction "6_6") (pintype "unspecified"))
      (node (ref "LED3") (pin "1") (pinfunction "-_1") (pintype "unspecified"))
      (node (ref "R22") (pin "1") (pinfunction "1_1") (pintype "input"))
    )
    (net (code "65") (name "SCK") (class "Default")
      (node (ref "H1") (pin "1") (pinfunction "1_1") (pintype "unspecified"))
      (node (ref "U1") (pin "9") (pinfunction "PB1(PCINT1/SCLK)_9") (pintype "unspecified"))
      (node (ref "XP1") (pin "3") (pinfunction "3_3") (pintype "unspecified"))
    )
    (net (code "66") (name "TXO") (class "Default")
      (node (ref "H1") (pin "5") (pinfunction "5_5") (pintype "unspecified"))
      (node (ref "U1") (pin "21") (pinfunction "PD3(TXD1/INT3)_21") (pintype "unspecified"))
    )
    (net (code "67") (name "UVCC") (class "Default")
      (node (ref "U1") (pin "2") (pinfunction "UVcc_2") (pintype "unspecified"))
      (node (ref "U1") (pin "7") (pinfunction "VBus_7") (pintype "unspecified"))
      (node (ref "U4") (pin "1") (pinfunction "1_1") (pintype "unspecified"))
      (node (ref "U6") (pin "1") (pinfunction "1_1") (pintype "unspecified"))
      (node (ref "USBC1") (pin "A4") (pinfunction "VBUS_A4") (pintype "unspecified"))
      (node (ref "USBC1") (pin "A9") (pinfunction "VBUS_A9") (pintype "unspecified"))
      (node (ref "USBC1") (pin "B4") (pinfunction "VBUS_B4") (pintype "unspecified"))
      (node (ref "USBC1") (pin "B9") (pinfunction "VBUS_B9") (pintype "unspecified"))
    )
    (net (code "68") (name "VCC") (class "Default")
      (node (ref "C13") (pin "1") (pinfunction "1_1") (pintype "input"))
      (node (ref "C15") (pin "1") (pinfunction "1_1") (pintype "input"))
      (node (ref "C2") (pin "1") (pinfunction "1_1") (pintype "input"))
      (node (ref "C3") (pin "1") (pinfunction "1_1") (pintype "unspecified"))
      (node (ref "C4") (pin "1") (pinfunction "1_1") (pintype "input"))
      (node (ref "C8") (pin "1") (pinfunction "1_1") (pintype "input"))
      (node (ref "H1") (pin "10") (pinfunction "10_10") (pintype "unspecified"))
      (node (ref "H1") (pin "11") (pinfunction "11_11") (pintype "unspecified"))
      (node (ref "H1") (pin "12") (pinfunction "12_12") (pintype "unspecified"))
      (node (ref "H1") (pin "9") (pinfunction "9_9") (pintype "unspecified"))
      (node (ref "LED1") (pin "1") (pinfunction "A_1") (pintype "unspecified"))
      (node (ref "LED2") (pin "1") (pinfunction "VDD_1") (pintype "unspecified"))
      (node (ref "LED3") (pin "2") (pinfunction "+_2") (pintype "unspecified"))
      (node (ref "LED4") (pin "2") (pinfunction "+_2") (pintype "unspecified"))
      (node (ref "LED5") (pin "1") (pinfunction "A_1") (pintype "unspecified"))
      (node (ref "Q1") (pin "2") (pinfunction "S_2") (pintype "unspecified"))
      (node (ref "R24") (pin "1") (pinfunction "1_1") (pintype "input"))
      (node (ref "SW2") (pin "1") (pinfunction "A1_1") (pintype "input"))
      (node (ref "SW2") (pin "2") (pinfunction "A2_2") (pintype "input"))
      (node (ref "SW2") (pin "3") (pinfunction "A3_3") (pintype "input"))
      (node (ref "SW2") (pin "4") (pinfunction "A4_4") (pintype "input"))
      (node (ref "SW2") (pin "5") (pinfunction "A5_5") (pintype "input"))
      (node (ref "SW2") (pin "6") (pinfunction "A6_6") (pintype "input"))
      (node (ref "SW2") (pin "7") (pinfunction "A7_7") (pintype "input"))
      (node (ref "SW2") (pin "8") (pinfunction "A8_8") (pintype "input"))
      (node (ref "U1") (pin "14") (pinfunction "VCC_14") (pintype "unspecified"))
      (node (ref "U1") (pin "24") (pinfunction "AVCC_24") (pintype "unspecified"))
      (node (ref "U1") (pin "34") (pinfunction "VCC_34") (pintype "unspecified"))
      (node (ref "U1") (pin "44") (pinfunction "AVCC_44") (pintype "unspecified"))
      (node (ref "U2") (pin "5") (pinfunction "OUT_5") (pintype "unspecified"))
      (node (ref "U5") (pin "3") (pinfunction "OUT_3") (pintype "passive"))
      (node (ref "XP1") (pin "2") (pinfunction "2_2") (pintype "unspecified"))
    )
    (net (code "69") (name "XTAL1") (class "Default")
      (node (ref "C6") (pin "2") (pinfunction "2_2") (pintype "input"))
      (node (ref "U1") (pin "17") (pinfunction "XTAL1_17") (pintype "unspecified"))
      (node (ref "X1") (pin "1") (pinfunction "OSC1_1") (pintype "unspecified"))
    )
    (net (code "70") (name "XTAL2") (class "Default")
      (node (ref "C5") (pin "2") (pinfunction "2_2") (pintype "input"))
      (node (ref "U1") (pin "16") (pinfunction "XTAL2_16") (pintype "unspecified"))
      (node (ref "X1") (pin "3") (pinfunction "OSC2_3") (pintype "unspecified"))
    )
    (net (code "71") (name "unconnected-(SW4-Pad3)") (class "Default")
      (node (ref "SW4") (pin "3") (pinfunction "3_3") (pintype "unspecified+no_connect"))
    )
    (net (code "72") (name "unconnected-(U2-BYP-Pad4)") (class "Default")
      (node (ref "U2") (pin "4") (pinfunction "BYP_4") (pintype "unspecified+no_connect"))
    )
    (net (code "73") (name "unconnected-(U5-TAB-Pad4)") (class "Default")
      (node (ref "U5") (pin "4") (pinfunction "TAB_4") (pintype "passive"))
    )
    (net (code "74") (name "unconnected-(U7-TAB-Pad4)") (class "Default")
      (node (ref "U7") (pin "4") (pinfunction "TAB_4") (pintype "unspecified"))
    )
    (net (code "75") (name "unconnected-(USBC1-Pad0)") (class "Default")
      (node (ref "USBC1") (pin "0") (pinfunction "0_0") (pintype "unspecified"))
    )
    (net (code "76") (name "unconnected-(USBC1-Pad0)_1") (class "Default")
      (node (ref "USBC1") (pin "0") (pinfunction "0_0") (pintype "unspecified"))
    )
    (net (code "77") (name "unconnected-(USBC1-Pad0)_2") (class "Default")
      (node (ref "USBC1") (pin "0") (pinfunction "0_0") (pintype "unspecified"))
    )
    (net (code "78") (name "unconnected-(USBC1-Pad0)_3") (class "Default")
      (node (ref "USBC1") (pin "0") (pinfunction "0_0") (pintype "unspecified"))
    )
    (net (code "79") (name "unconnected-(USBC1-SBU1-PadA8)") (class "Default")
      (node (ref "USBC1") (pin "A8") (pinfunction "SBU1_A8") (pintype "unspecified+no_connect"))
    )
    (net (code "80") (name "unconnected-(USBC1-SBU2-PadB8)") (class "Default")
      (node (ref "USBC1") (pin "B8") (pinfunction "SBU2_B8") (pintype "unspecified+no_connect"))
    )
    (net (code "81") (name "unconnected-(X1-GND-Pad2)") (class "Default")
      (node (ref "X1") (pin "2") (pinfunction "GND_2") (pintype "unspecified+no_connect"))
    )
    (net (code "82") (name "unconnected-(X1-GND-Pad4)") (class "Default")
      (node (ref "X1") (pin "4") (pinfunction "GND_4") (pintype "unspecified+no_connect"))
    )
  )
)
